# X8-Backplane.net
KiCad netlist of a schematic drawn in EAGLE
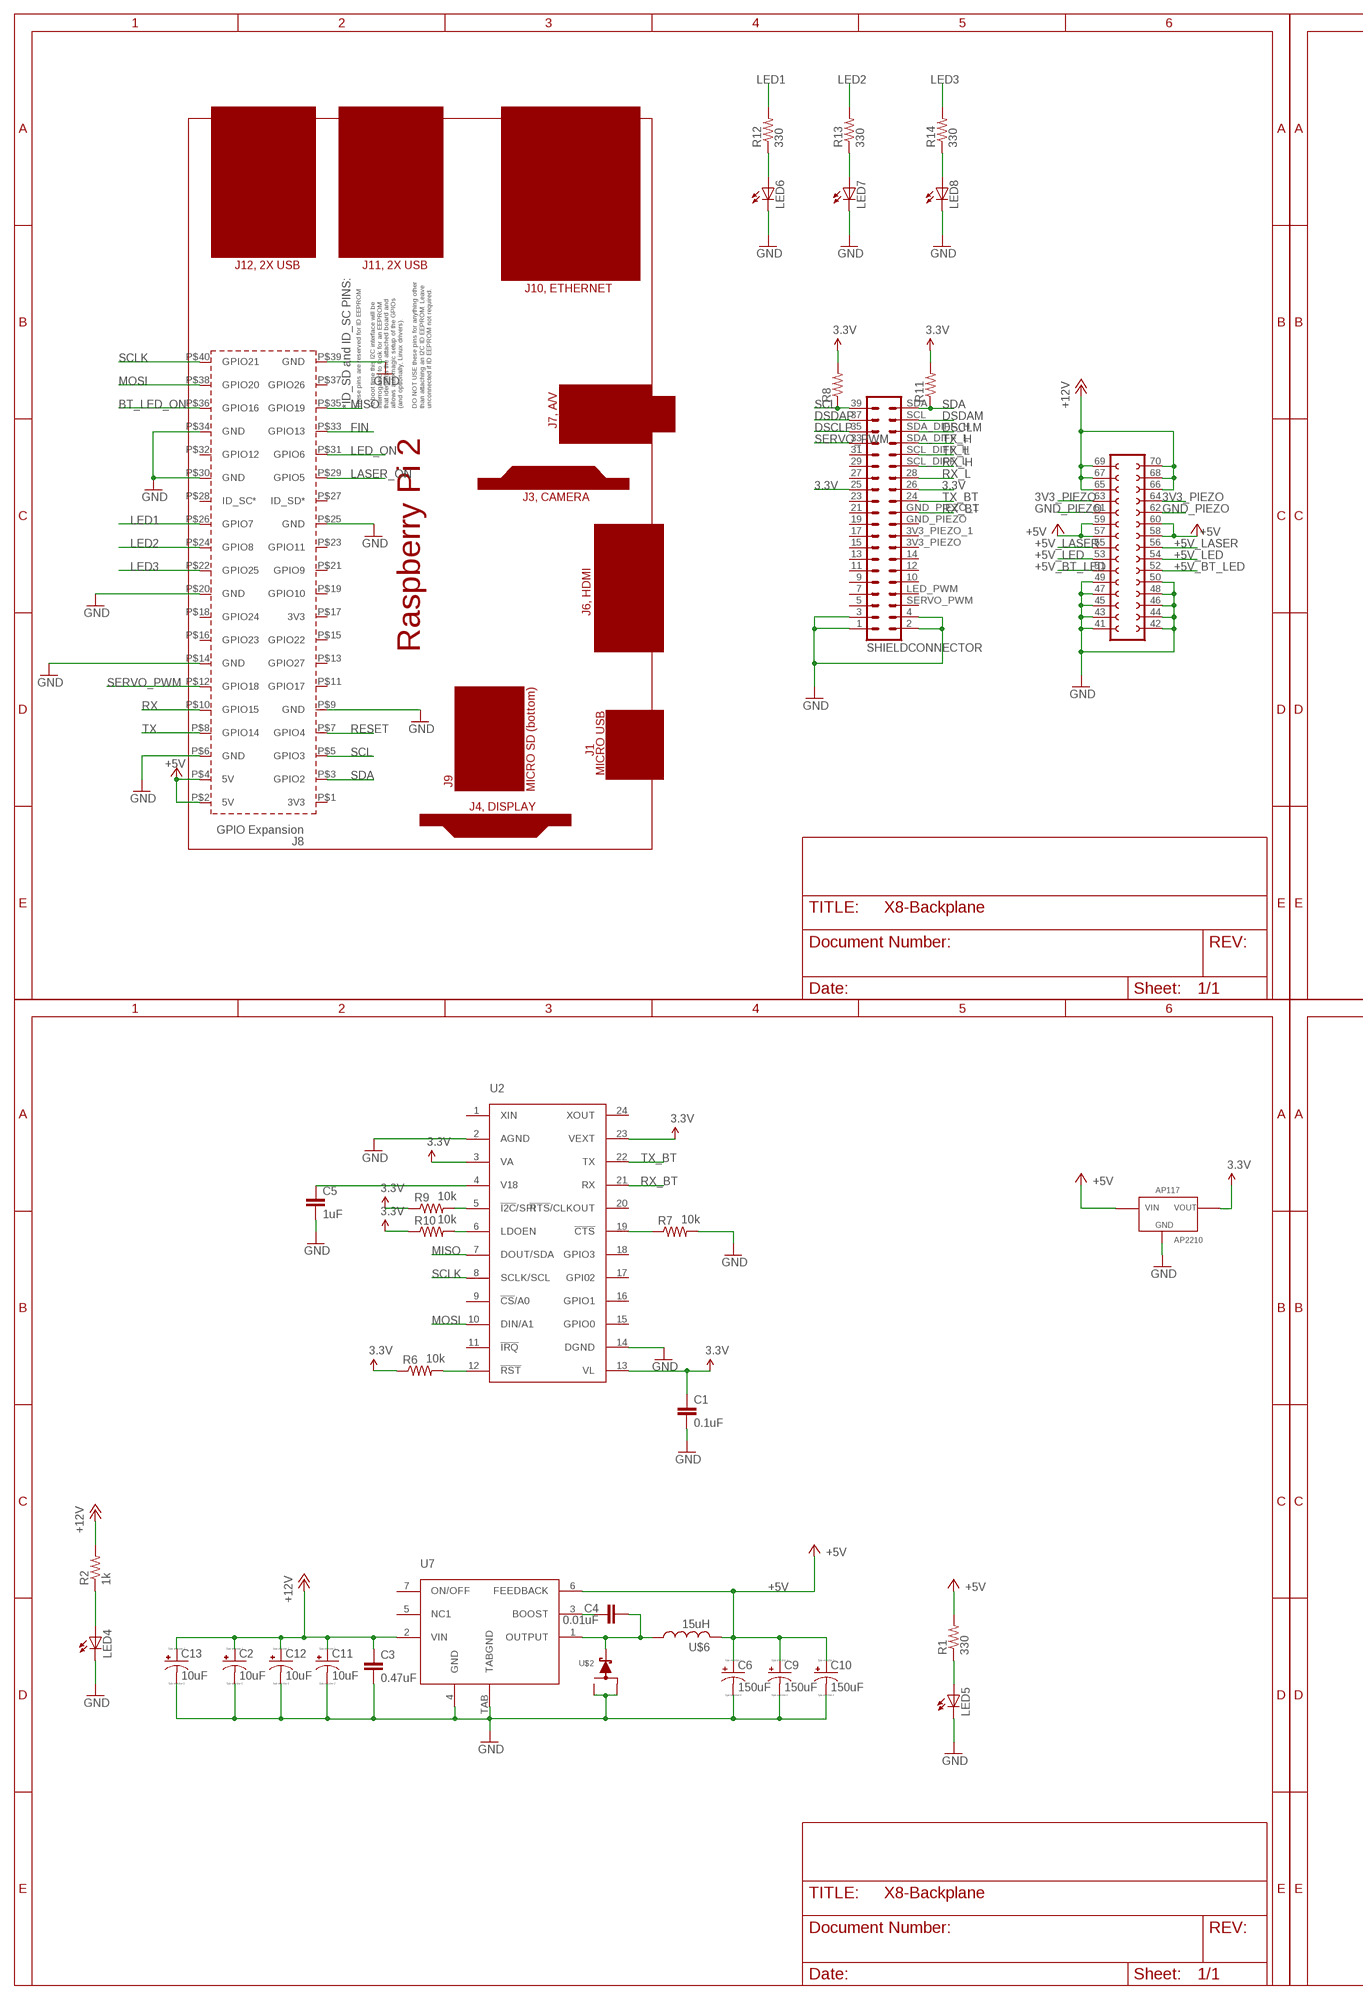
[diagram p0: schematic, sheet 1, part 1 of 2]
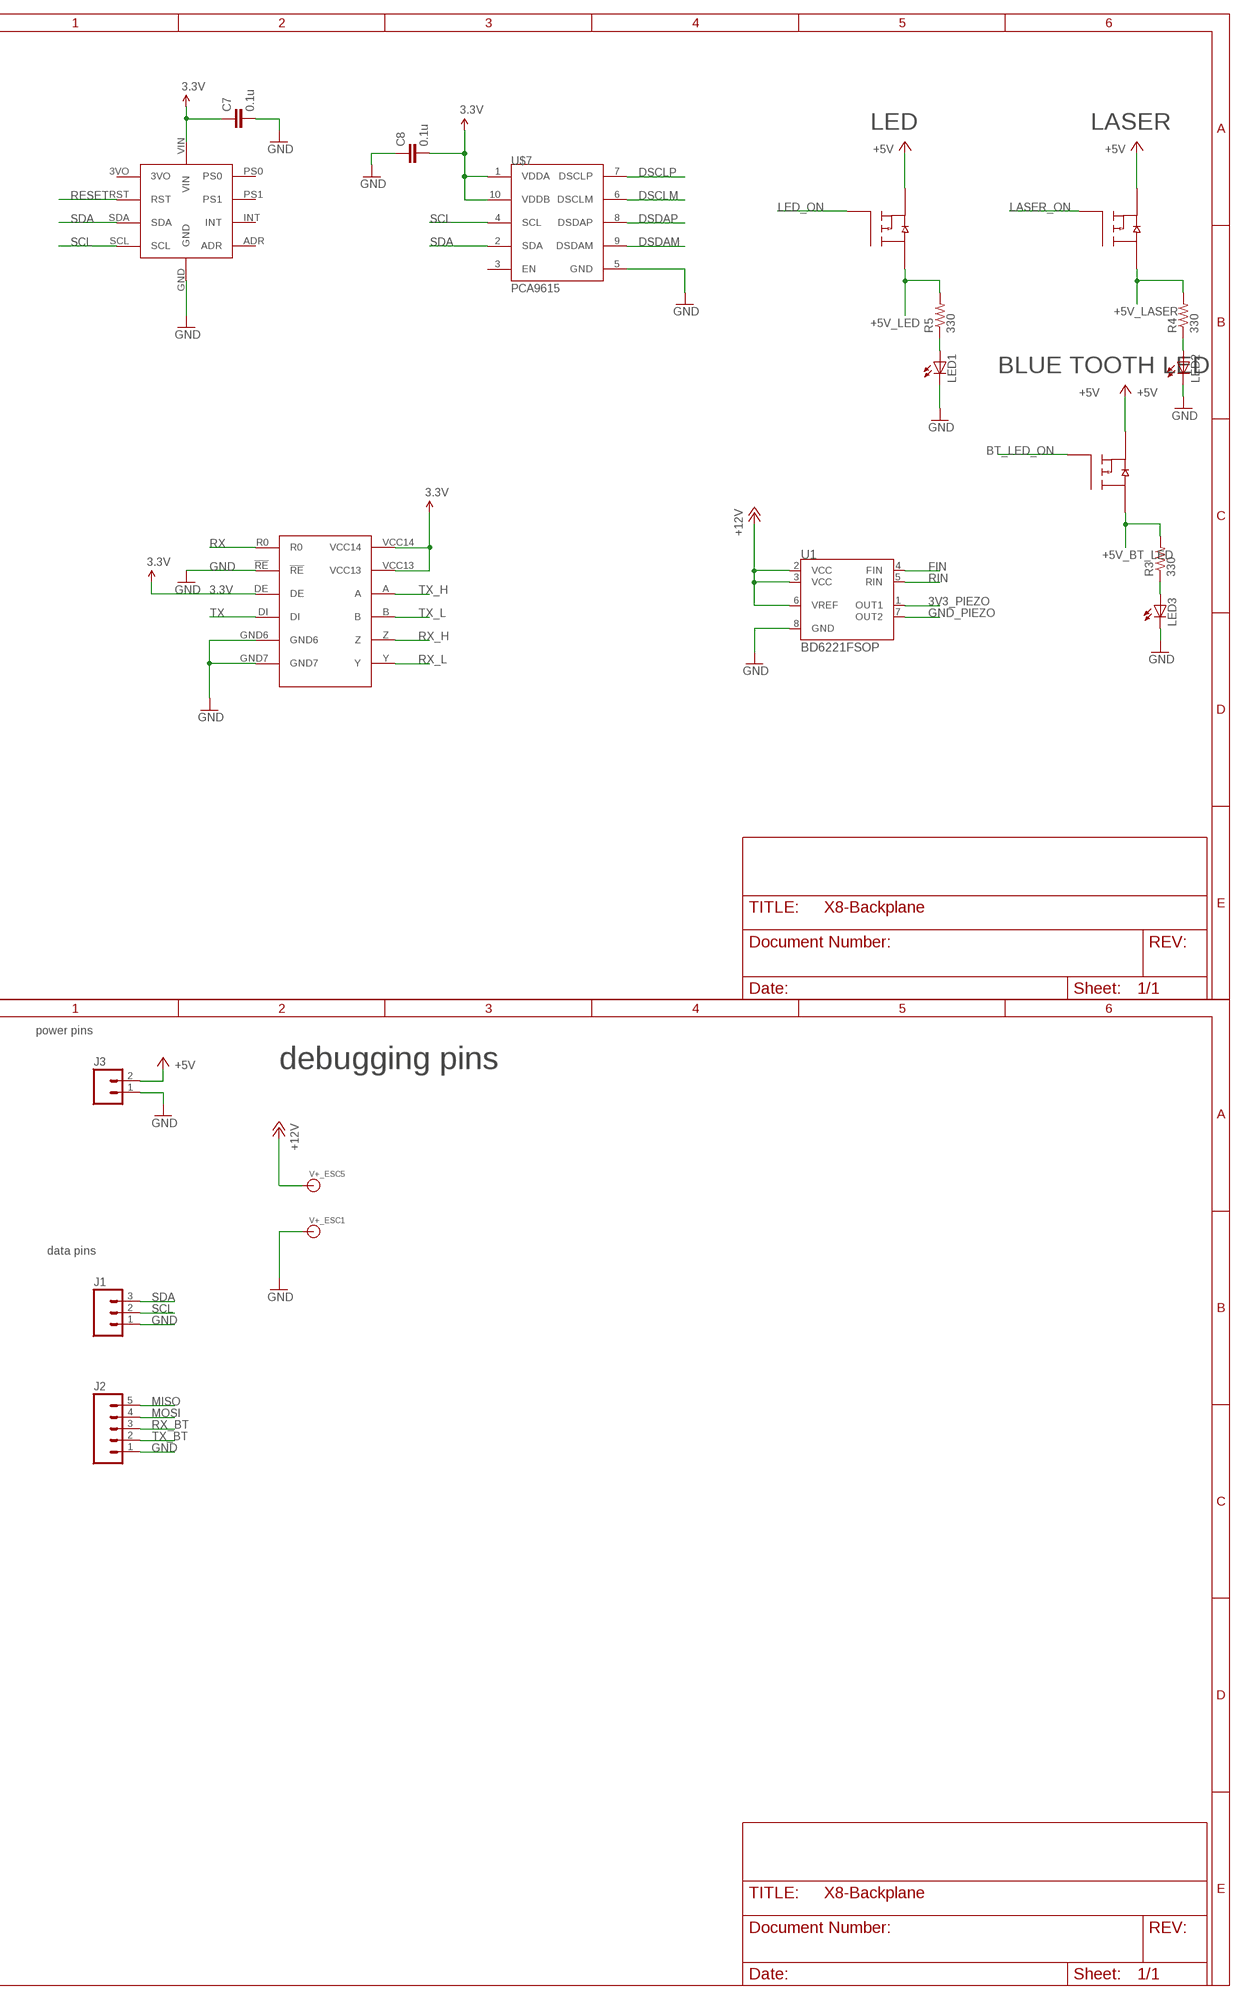
[diagram p1: schematic, sheet 1, part 2 of 2]

(export (version "E")
  (design (tool "Eeschema 10.0.6"))
  (components
    (comp (ref "C1")
      (value "0.1uF")
      (footprint "eagle-import:0603-CAP")
      (libsource (lib "eagle-import") (part "0.1UF-25V(+80/-20%)(0603)"))
    )
    (comp (ref "C2")
      (value "10uF")
      (footprint "eagle-import:CTAN(7.30_4.30MM)")
      (libsource (lib "eagle-import") (part "C-TANTALUM(10UF_150UF)"))
    )
    (comp (ref "C3")
      (value "0.47uF")
      (footprint "eagle-import:0603")
      (libsource (lib "eagle-import") (part "0.18UF-0603-10V-10%"))
    )
    (comp (ref "C4")
      (value "0.01uF")
      (footprint "eagle-import:0603-CAP")
      (libsource (lib "eagle-import") (part "CAP0603-CAP"))
    )
    (comp (ref "C5")
      (value "1uF")
      (footprint "eagle-import:0603-CAP")
      (libsource (lib "eagle-import") (part "0.1UF-25V(+80/-20%)(0603)"))
    )
    (comp (ref "C6")
      (value "150uF")
      (footprint "eagle-import:CTAN(7.30_4.30MM)")
      (libsource (lib "eagle-import") (part "C-TANTALUM(10UF_150UF)"))
    )
    (comp (ref "C7")
      (value "0.1u")
      (footprint "eagle-import:0603-CAP")
      (libsource (lib "eagle-import") (part "CAP0603-CAP"))
    )
    (comp (ref "C8")
      (value "0.1u")
      (footprint "eagle-import:0603-CAP")
      (libsource (lib "eagle-import") (part "CAP0603-CAP"))
    )
    (comp (ref "C9")
      (value "150uF")
      (footprint "eagle-import:CTAN(7.30_4.30MM)")
      (libsource (lib "eagle-import") (part "C-TANTALUM(10UF_150UF)"))
    )
    (comp (ref "C10")
      (value "150uF")
      (footprint "eagle-import:CTAN(7.30_4.30MM)")
      (libsource (lib "eagle-import") (part "C-TANTALUM(10UF_150UF)"))
    )
    (comp (ref "C11")
      (value "10uF")
      (footprint "eagle-import:CTAN(7.30_4.30MM)")
      (libsource (lib "eagle-import") (part "C-TANTALUM(10UF_150UF)"))
    )
    (comp (ref "C12")
      (value "10uF")
      (footprint "eagle-import:CTAN(7.30_4.30MM)")
      (libsource (lib "eagle-import") (part "C-TANTALUM(10UF_150UF)"))
    )
    (comp (ref "C13")
      (value "10uF")
      (footprint "eagle-import:CTAN(7.30_4.30MM)")
      (libsource (lib "eagle-import") (part "C-TANTALUM(10UF_150UF)"))
    )
    (comp (ref "J1")
      (value "M03PTH")
      (footprint "eagle-import:1X03")
      (libsource (lib "eagle-import") (part "M03PTH"))
    )
    (comp (ref "J2")
      (value "M05PTH")
      (footprint "eagle-import:1X05")
      (libsource (lib "eagle-import") (part "M05PTH"))
    )
    (comp (ref "J3")
      (value "M02PTH")
      (footprint "eagle-import:1X02")
      (libsource (lib "eagle-import") (part "M02PTH"))
    )
    (comp (ref "LED1")
      (value "LEDSML0603")
      (footprint "eagle-import:SML0603")
      (libsource (lib "eagle-import") (part "LEDSML0603"))
    )
    (comp (ref "LED2")
      (value "LEDSML0603")
      (footprint "eagle-import:SML0603")
      (libsource (lib "eagle-import") (part "LEDSML0603"))
    )
    (comp (ref "LED3")
      (value "LEDSML0603")
      (footprint "eagle-import:SML0603")
      (libsource (lib "eagle-import") (part "LEDSML0603"))
    )
    (comp (ref "LED4")
      (value "LEDSML0603")
      (footprint "eagle-import:SML0603")
      (libsource (lib "eagle-import") (part "LEDSML0603"))
    )
    (comp (ref "LED5")
      (value "LEDSML0603")
      (footprint "eagle-import:SML0603")
      (libsource (lib "eagle-import") (part "LEDSML0603"))
    )
    (comp (ref "LED6")
      (value "LEDSML0603")
      (footprint "eagle-import:SML0603")
      (libsource (lib "eagle-import") (part "LEDSML0603"))
    )
    (comp (ref "LED7")
      (value "LEDSML0603")
      (footprint "eagle-import:SML0603")
      (libsource (lib "eagle-import") (part "LEDSML0603"))
    )
    (comp (ref "LED8")
      (value "LEDSML0603")
      (footprint "eagle-import:SML0603")
      (libsource (lib "eagle-import") (part "LEDSML0603"))
    )
    (comp (ref "PCB1")
      (value "RPI2")
      (footprint "eagle-import:RPI2")
      (libsource (lib "eagle-import") (part "RPI2"))
    )
    (comp (ref "R1")
      (value "330")
      (footprint "eagle-import:R0603")
      (libsource (lib "eagle-import") (part "R-US_R0603"))
    )
    (comp (ref "R2")
      (value "1k")
      (footprint "eagle-import:R0603")
      (libsource (lib "eagle-import") (part "R-US_R0603"))
    )
    (comp (ref "R3")
      (value "330")
      (footprint "eagle-import:R0603")
      (libsource (lib "eagle-import") (part "R-US_R0603"))
    )
    (comp (ref "R4")
      (value "330")
      (footprint "eagle-import:R0603")
      (libsource (lib "eagle-import") (part "R-US_R0603"))
    )
    (comp (ref "R5")
      (value "330")
      (footprint "eagle-import:R0603")
      (libsource (lib "eagle-import") (part "R-US_R0603"))
    )
    (comp (ref "R6")
      (value "10k")
      (footprint "eagle-import:0603-RES")
      (libsource (lib "eagle-import") (part "RESISTOR0603-RES"))
    )
    (comp (ref "R7")
      (value "10k")
      (footprint "eagle-import:0603-RES")
      (libsource (lib "eagle-import") (part "RESISTOR0603-RES"))
    )
    (comp (ref "R8")
      (value "RESISTOR0603-RES")
      (footprint "eagle-import:0603-RES")
      (libsource (lib "eagle-import") (part "RESISTOR0603-RES"))
    )
    (comp (ref "R9")
      (value "10k")
      (footprint "eagle-import:0603-RES")
      (libsource (lib "eagle-import") (part "RESISTOR0603-RES"))
    )
    (comp (ref "R10")
      (value "10k")
      (footprint "eagle-import:0603-RES")
      (libsource (lib "eagle-import") (part "RESISTOR0603-RES"))
    )
    (comp (ref "R11")
      (value "RESISTOR0603-RES")
      (footprint "eagle-import:0603-RES")
      (libsource (lib "eagle-import") (part "RESISTOR0603-RES"))
    )
    (comp (ref "R12")
      (value "330")
      (footprint "eagle-import:R0603")
      (libsource (lib "eagle-import") (part "R-US_R0603"))
    )
    (comp (ref "R13")
      (value "330")
      (footprint "eagle-import:R0603")
      (libsource (lib "eagle-import") (part "R-US_R0603"))
    )
    (comp (ref "R14")
      (value "330")
      (footprint "eagle-import:R0603")
      (libsource (lib "eagle-import") (part "R-US_R0603"))
    )
    (comp (ref "U$1")
      (value "MAX3491")
      (footprint "eagle-import:MAX3491")
      (libsource (lib "eagle-import") (part "MAX3491"))
    )
    (comp (ref "U$2")
      (value "SWITCHMODE_SCHOTTKY")
      (footprint "eagle-import:DPAK-3")
      (libsource (lib "eagle-import") (part "SWITCHMODE_SCHOTTKY"))
    )
    (comp (ref "U$3")
      (value "BNO055_9DOF_BREAKOUT")
      (footprint "eagle-import:BNO055")
      (libsource (lib "eagle-import") (part "BNO055_9DOF_BREAKOUT"))
    )
    (comp (ref "U$4")
      (value "SHIELDCONNECTOR")
      (footprint "eagle-import:20X2PIN")
      (libsource (lib "eagle-import") (part "SHIELDCONNECTOR"))
    )
    (comp (ref "U$5")
      (value "AP2210")
      (footprint "eagle-import:SOT-23-3")
      (libsource (lib "eagle-import") (part "AP2210"))
    )
    (comp (ref "U$6")
      (value "15uH")
      (footprint "eagle-import:HCMA1305")
      (libsource (lib "eagle-import") (part "HCMA1305"))
    )
    (comp (ref "U$7")
      (value "PCA9615")
      (footprint "eagle-import:MSOP_10")
      (libsource (lib "eagle-import") (part "PCA9615"))
    )
    (comp (ref "U1")
      (value "BD6221FSOP")
      (footprint "eagle-import:SOP8")
      (libsource (lib "eagle-import") (part "BD6221FSOP"))
    )
    (comp (ref "U2")
      (value "MAX3107SSOP")
      (footprint "eagle-import:SSOP-24")
      (libsource (lib "eagle-import") (part "MAX3107SSOP"))
    )
    (comp (ref "U4")
      (value "FQB27P06")
      (footprint "eagle-import:TO263-3")
      (libsource (lib "eagle-import") (part "FQB27P06"))
    )
    (comp (ref "U5")
      (value "FQB27P06")
      (footprint "eagle-import:TO263-3")
      (libsource (lib "eagle-import") (part "FQB27P06"))
    )
    (comp (ref "U6")
      (value "FQB27P06")
      (footprint "eagle-import:TO263-3")
      (libsource (lib "eagle-import") (part "FQB27P06"))
    )
    (comp (ref "U7")
      (value "LM2678")
      (footprint "eagle-import:LM2678")
      (libsource (lib "eagle-import") (part "LM2678"))
    )
    (comp (ref "V+_ESC1")
      (value "BANANA_CONN")
      (footprint "eagle-import:BANANA_CONN")
      (libsource (lib "eagle-import") (part "BANANA_CONN"))
    )
    (comp (ref "V+_ESC5")
      (value "BANANA_CONN")
      (footprint "eagle-import:BANANA_CONN")
      (libsource (lib "eagle-import") (part "BANANA_CONN"))
    )
  )
  (nets
    (net (code "1") (name "+5V") (class "Default")
      (node (ref "C10") (pin "+") (pinfunction "+_+") (pintype "passive"))
      (node (ref "C6") (pin "+") (pinfunction "+_+") (pintype "passive"))
      (node (ref "C9") (pin "+") (pinfunction "+_+") (pintype "passive"))
      (node (ref "J3") (pin "2") (pinfunction "2_2") (pintype "passive"))
      (node (ref "PCB1") (pin "P$2") (pinfunction "5V_P$2") (pintype "bidirectional"))
      (node (ref "PCB1") (pin "P$4") (pinfunction "5V_P$4") (pintype "bidirectional"))
      (node (ref "R1") (pin "2") (pinfunction "2_2") (pintype "passive"))
      (node (ref "U$4") (pin "57") (pinfunction "17_57") (pintype "passive"))
      (node (ref "U$4") (pin "58") (pinfunction "18_58") (pintype "passive"))
      (node (ref "U$4") (pin "59") (pinfunction "19_59") (pintype "passive"))
      (node (ref "U$4") (pin "60") (pinfunction "20_60") (pintype "passive"))
      (node (ref "U$5") (pin "VIN") (pinfunction "VIN_VIN") (pintype "input"))
      (node (ref "U$6") (pin "P$2") (pinfunction "2_P$2") (pintype "passive"))
      (node (ref "U4") (pin "3") (pinfunction "S2_3") (pintype "bidirectional"))
      (node (ref "U5") (pin "3") (pinfunction "S2_3") (pintype "bidirectional"))
      (node (ref "U6") (pin "3") (pinfunction "S2_3") (pintype "bidirectional"))
      (node (ref "U7") (pin "6") (pinfunction "FEEDBACK_6") (pintype "bidirectional"))
    )
    (net (code "2") (name "+12V") (class "Default")
      (node (ref "C11") (pin "+") (pinfunction "+_+") (pintype "passive"))
      (node (ref "C12") (pin "+") (pinfunction "+_+") (pintype "passive"))
      (node (ref "C13") (pin "+") (pinfunction "+_+") (pintype "passive"))
      (node (ref "C2") (pin "+") (pinfunction "+_+") (pintype "passive"))
      (node (ref "C3") (pin "1") (pinfunction "1_1") (pintype "passive"))
      (node (ref "R2") (pin "2") (pinfunction "2_2") (pintype "passive"))
      (node (ref "U$4") (pin "65") (pinfunction "25_65") (pintype "passive"))
      (node (ref "U$4") (pin "66") (pinfunction "26_66") (pintype "passive"))
      (node (ref "U$4") (pin "67") (pinfunction "27_67") (pintype "passive"))
      (node (ref "U$4") (pin "68") (pinfunction "28_68") (pintype "passive"))
      (node (ref "U$4") (pin "69") (pinfunction "12V_69") (pintype "passive"))
      (node (ref "U$4") (pin "70") (pinfunction "30_70") (pintype "passive"))
      (node (ref "U1") (pin "2") (pinfunction "VCC_2") (pintype "power_in"))
      (node (ref "U1") (pin "3") (pinfunction "VCC_3") (pintype "power_in"))
      (node (ref "U1") (pin "6") (pinfunction "VREF_6") (pintype "bidirectional"))
      (node (ref "U7") (pin "2") (pinfunction "VIN_2") (pintype "bidirectional"))
      (node (ref "V+_ESC5") (pin "P$1") (pinfunction "1_P$1") (pintype "passive"))
    )
    (net (code "3") (name "/+5V_BT_LED") (class "Default")
      (node (ref "R3") (pin "2") (pinfunction "2_2") (pintype "passive"))
      (node (ref "U$4") (pin "51") (pinfunction "11_51") (pintype "passive"))
      (node (ref "U$4") (pin "52") (pinfunction "12_52") (pintype "passive"))
      (node (ref "U6") (pin "TAB") (pinfunction "D2_TAB") (pintype "bidirectional"))
    )
    (net (code "4") (name "/+5V_LASER") (class "Default")
      (node (ref "R4") (pin "2") (pinfunction "2_2") (pintype "passive"))
      (node (ref "U$4") (pin "55") (pinfunction "15_55") (pintype "passive"))
      (node (ref "U$4") (pin "56") (pinfunction "16_56") (pintype "passive"))
      (node (ref "U5") (pin "TAB") (pinfunction "D2_TAB") (pintype "bidirectional"))
    )
    (net (code "5") (name "/+5V_LED") (class "Default")
      (node (ref "R5") (pin "2") (pinfunction "2_2") (pintype "passive"))
      (node (ref "U$4") (pin "53") (pinfunction "13_53") (pintype "passive"))
      (node (ref "U$4") (pin "54") (pinfunction "14_54") (pintype "passive"))
      (node (ref "U4") (pin "TAB") (pinfunction "D2_TAB") (pintype "bidirectional"))
    )
    (net (code "6") (name "/3V3_PIEZO") (class "Default")
      (node (ref "U$4") (pin "63") (pinfunction "23_63") (pintype "passive"))
      (node (ref "U$4") (pin "64") (pinfunction "24_64") (pintype "passive"))
      (node (ref "U1") (pin "1") (pinfunction "OUT1_1") (pintype "output"))
    )
    (net (code "7") (name "/BT_LED_ON") (class "Default")
      (node (ref "PCB1") (pin "P$36") (pinfunction "GPIO16_P$36") (pintype "bidirectional"))
      (node (ref "U6") (pin "1") (pinfunction "G2_1") (pintype "bidirectional"))
    )
    (net (code "8") (name "/DSCLM") (class "Default")
      (node (ref "U$4") (pin "SDA_DIFF_H") (pinfunction "SDA_DIFF_H_SDA_DIFF_H") (pintype "passive"))
      (node (ref "U$7") (pin "6") (pinfunction "DSCLM_6") (pintype "bidirectional"))
    )
    (net (code "9") (name "/DSCLP") (class "Default")
      (node (ref "U$4") (pin "35") (pinfunction "35_35") (pintype "passive"))
      (node (ref "U$7") (pin "7") (pinfunction "DSCLP_7") (pintype "bidirectional"))
    )
    (net (code "10") (name "/DSDAM") (class "Default")
      (node (ref "U$4") (pin "SCL") (pinfunction "SCL_SCL") (pintype "passive"))
      (node (ref "U$7") (pin "9") (pinfunction "DSDAM_9") (pintype "bidirectional"))
    )
    (net (code "11") (name "/DSDAP") (class "Default")
      (node (ref "U$4") (pin "37") (pinfunction "37_37") (pintype "passive"))
      (node (ref "U$7") (pin "8") (pinfunction "DSDAP_8") (pintype "bidirectional"))
    )
    (net (code "12") (name "/FIN") (class "Default")
      (node (ref "PCB1") (pin "P$33") (pinfunction "GPIO13_P$33") (pintype "bidirectional"))
      (node (ref "U1") (pin "4") (pinfunction "FIN_4") (pintype "input"))
    )
    (net (code "13") (name "/GND_PIEZO") (class "Default")
      (node (ref "U$4") (pin "61") (pinfunction "21_61") (pintype "passive"))
      (node (ref "U$4") (pin "62") (pinfunction "22_62") (pintype "passive"))
      (node (ref "U1") (pin "7") (pinfunction "OUT2_7") (pintype "output"))
    )
    (net (code "14") (name "/LASER_ON") (class "Default")
      (node (ref "PCB1") (pin "P$29") (pinfunction "GPIO5_P$29") (pintype "bidirectional"))
      (node (ref "U5") (pin "1") (pinfunction "G2_1") (pintype "bidirectional"))
    )
    (net (code "15") (name "/LED1") (class "Default")
      (node (ref "PCB1") (pin "P$26") (pinfunction "GPIO7_P$26") (pintype "bidirectional"))
      (node (ref "R12") (pin "2") (pinfunction "2_2") (pintype "passive"))
    )
    (net (code "16") (name "/LED2") (class "Default")
      (node (ref "PCB1") (pin "P$24") (pinfunction "GPIO8_P$24") (pintype "bidirectional"))
      (node (ref "R13") (pin "2") (pinfunction "2_2") (pintype "passive"))
    )
    (net (code "17") (name "/LED3") (class "Default")
      (node (ref "PCB1") (pin "P$22") (pinfunction "GPIO25_P$22") (pintype "bidirectional"))
      (node (ref "R14") (pin "2") (pinfunction "2_2") (pintype "passive"))
    )
    (net (code "18") (name "/LED_ON") (class "Default")
      (node (ref "PCB1") (pin "P$31") (pinfunction "GPIO6_P$31") (pintype "bidirectional"))
      (node (ref "U4") (pin "1") (pinfunction "G2_1") (pintype "bidirectional"))
    )
    (net (code "19") (name "/MISO") (class "Default")
      (node (ref "J2") (pin "5") (pinfunction "5_5") (pintype "passive"))
      (node (ref "PCB1") (pin "P$35") (pinfunction "GPIO19_P$35") (pintype "bidirectional"))
      (node (ref "U2") (pin "7") (pinfunction "DOUT/SDA_7") (pintype "bidirectional"))
    )
    (net (code "20") (name "/MOSI") (class "Default")
      (node (ref "J2") (pin "4") (pinfunction "4_4") (pintype "passive"))
      (node (ref "PCB1") (pin "P$38") (pinfunction "GPIO20_P$38") (pintype "bidirectional"))
      (node (ref "U2") (pin "10") (pinfunction "DIN/A1_10") (pintype "bidirectional"))
    )
    (net (code "21") (name "/RESET") (class "Default")
      (node (ref "PCB1") (pin "P$7") (pinfunction "GPIO4_P$7") (pintype "bidirectional"))
      (node (ref "U$3") (pin "RST") (pinfunction "RST_RST") (pintype "bidirectional"))
    )
    (net (code "22") (name "/RIN") (class "Default")
      (node (ref "U1") (pin "5") (pinfunction "RIN_5") (pintype "input"))
    )
    (net (code "23") (name "/RX") (class "Default")
      (node (ref "PCB1") (pin "P$10") (pinfunction "GPIO15_P$10") (pintype "bidirectional"))
      (node (ref "U$1") (pin "R0") (pinfunction "R0_R0") (pintype "bidirectional"))
    )
    (net (code "24") (name "/RX_BT") (class "Default")
      (node (ref "J2") (pin "3") (pinfunction "3_3") (pintype "passive"))
      (node (ref "U$4") (pin "GND_PIEZO_1") (pinfunction "GND_PIEZO_1_GND_PIEZO_1") (pintype "passive"))
      (node (ref "U2") (pin "21") (pinfunction "RX_21") (pintype "bidirectional"))
    )
    (net (code "25") (name "/RX_H") (class "Default")
      (node (ref "U$1") (pin "Z") (pinfunction "Z_Z") (pintype "bidirectional"))
      (node (ref "U$4") (pin "SCL_DIFF_L") (pinfunction "SCL_DIFF_L_SCL_DIFF_L") (pintype "passive"))
    )
    (net (code "26") (name "/RX_L") (class "Default")
      (node (ref "U$1") (pin "Y") (pinfunction "Y_Y") (pintype "bidirectional"))
      (node (ref "U$4") (pin "28") (pinfunction "28_28") (pintype "passive"))
    )
    (net (code "27") (name "/SCL") (class "Default")
      (node (ref "J1") (pin "2") (pinfunction "2_2") (pintype "passive"))
      (node (ref "PCB1") (pin "P$5") (pinfunction "GPIO3_P$5") (pintype "bidirectional"))
      (node (ref "R8") (pin "1") (pinfunction "1_1") (pintype "passive"))
      (node (ref "U$3") (pin "SCL") (pinfunction "SCL_SCL") (pintype "bidirectional"))
      (node (ref "U$4") (pin "39") (pinfunction "39_39") (pintype "passive"))
      (node (ref "U$7") (pin "4") (pinfunction "SCL_4") (pintype "bidirectional"))
    )
    (net (code "28") (name "/SCLK") (class "Default")
      (node (ref "PCB1") (pin "P$40") (pinfunction "GPIO21_P$40") (pintype "bidirectional"))
      (node (ref "U2") (pin "8") (pinfunction "SCLK/SCL_8") (pintype "bidirectional"))
    )
    (net (code "29") (name "/SDA") (class "Default")
      (node (ref "J1") (pin "3") (pinfunction "3_3") (pintype "passive"))
      (node (ref "PCB1") (pin "P$3") (pinfunction "GPIO2_P$3") (pintype "bidirectional"))
      (node (ref "R11") (pin "1") (pinfunction "1_1") (pintype "passive"))
      (node (ref "U$3") (pin "SDA") (pinfunction "SDA_SDA") (pintype "bidirectional"))
      (node (ref "U$4") (pin "SDA") (pinfunction "SDA_SDA") (pintype "passive"))
      (node (ref "U$7") (pin "2") (pinfunction "SDA_2") (pintype "bidirectional"))
    )
    (net (code "30") (name "/SERVO_PWM") (class "Default")
      (node (ref "PCB1") (pin "P$12") (pinfunction "GPIO18_P$12") (pintype "bidirectional"))
      (node (ref "U$4") (pin "33") (pinfunction "33_33") (pintype "passive"))
    )
    (net (code "31") (name "/TX") (class "Default")
      (node (ref "PCB1") (pin "P$8") (pinfunction "GPIO14_P$8") (pintype "bidirectional"))
      (node (ref "U$1") (pin "DI") (pinfunction "DI_DI") (pintype "bidirectional"))
    )
    (net (code "32") (name "/TX_BT") (class "Default")
      (node (ref "J2") (pin "2") (pinfunction "2_2") (pintype "passive"))
      (node (ref "U$4") (pin "24") (pinfunction "24_24") (pintype "passive"))
      (node (ref "U2") (pin "22") (pinfunction "TX_22") (pintype "bidirectional"))
    )
    (net (code "33") (name "/TX_H") (class "Default")
      (node (ref "U$1") (pin "A") (pinfunction "A_A") (pintype "bidirectional"))
      (node (ref "U$4") (pin "SDA_DIFF_L") (pinfunction "SDA_DIFF_L_SDA_DIFF_L") (pintype "passive"))
    )
    (net (code "34") (name "/TX_L") (class "Default")
      (node (ref "U$1") (pin "B") (pinfunction "B_B") (pintype "bidirectional"))
      (node (ref "U$4") (pin "SCL_DIFF_H") (pinfunction "SCL_DIFF_H_SCL_DIFF_H") (pintype "passive"))
    )
    (net (code "35") (name "3.3V") (class "Default")
      (node (ref "C1") (pin "1") (pinfunction "1_1") (pintype "passive"))
      (node (ref "C7") (pin "1") (pinfunction "1_1") (pintype "passive"))
      (node (ref "C8") (pin "2") (pinfunction "2_2") (pintype "passive"))
      (node (ref "R10") (pin "1") (pinfunction "1_1") (pintype "passive"))
      (node (ref "R11") (pin "2") (pinfunction "2_2") (pintype "passive"))
      (node (ref "R6") (pin "1") (pinfunction "1_1") (pintype "passive"))
      (node (ref "R8") (pin "2") (pinfunction "2_2") (pintype "passive"))
      (node (ref "R9") (pin "1") (pinfunction "1_1") (pintype "passive"))
      (node (ref "U$1") (pin "DE") (pinfunction "DE_DE") (pintype "bidirectional"))
      (node (ref "U$1") (pin "VCC13") (pinfunction "VCC13_VCC13") (pintype "bidirectional"))
      (node (ref "U$1") (pin "VCC14") (pinfunction "VCC14_VCC14") (pintype "bidirectional"))
      (node (ref "U$3") (pin "VIN") (pinfunction "VIN_VIN") (pintype "bidirectional"))
      (node (ref "U$4") (pin "25") (pinfunction "25_25") (pintype "passive"))
      (node (ref "U$4") (pin "26") (pinfunction "26_26") (pintype "passive"))
      (node (ref "U$5") (pin "VOUT") (pinfunction "VOUT_VOUT") (pintype "output"))
      (node (ref "U$7") (pin "1") (pinfunction "VDDA_1") (pintype "bidirectional"))
      (node (ref "U$7") (pin "10") (pinfunction "VDDB_10") (pintype "bidirectional"))
      (node (ref "U2") (pin "13") (pinfunction "VL_13") (pintype "bidirectional"))
      (node (ref "U2") (pin "23") (pinfunction "VEXT_23") (pintype "bidirectional"))
      (node (ref "U2") (pin "3") (pinfunction "VA_3") (pintype "bidirectional"))
    )
    (net (code "36") (name "GND") (class "Default")
      (node (ref "C1") (pin "2") (pinfunction "2_2") (pintype "passive"))
      (node (ref "C10") (pin "-") (pinfunction "-_-") (pintype "passive"))
      (node (ref "C11") (pin "-") (pinfunction "-_-") (pintype "passive"))
      (node (ref "C12") (pin "-") (pinfunction "-_-") (pintype "passive"))
      (node (ref "C13") (pin "-") (pinfunction "-_-") (pintype "passive"))
      (node (ref "C2") (pin "-") (pinfunction "-_-") (pintype "passive"))
      (node (ref "C3") (pin "2") (pinfunction "2_2") (pintype "passive"))
      (node (ref "C5") (pin "2") (pinfunction "2_2") (pintype "passive"))
      (node (ref "C6") (pin "-") (pinfunction "-_-") (pintype "passive"))
      (node (ref "C7") (pin "2") (pinfunction "2_2") (pintype "passive"))
      (node (ref "C8") (pin "1") (pinfunction "1_1") (pintype "passive"))
      (node (ref "C9") (pin "-") (pinfunction "-_-") (pintype "passive"))
      (node (ref "J1") (pin "1") (pinfunction "1_1") (pintype "passive"))
      (node (ref "J2") (pin "1") (pinfunction "1_1") (pintype "passive"))
      (node (ref "J3") (pin "1") (pinfunction "1_1") (pintype "passive"))
      (node (ref "LED1") (pin "C") (pinfunction "C_C") (pintype "passive"))
      (node (ref "LED2") (pin "C") (pinfunction "C_C") (pintype "passive"))
      (node (ref "LED3") (pin "C") (pinfunction "C_C") (pintype "passive"))
      (node (ref "LED4") (pin "C") (pinfunction "C_C") (pintype "passive"))
      (node (ref "LED5") (pin "C") (pinfunction "C_C") (pintype "passive"))
      (node (ref "LED6") (pin "C") (pinfunction "C_C") (pintype "passive"))
      (node (ref "LED7") (pin "C") (pinfunction "C_C") (pintype "passive"))
      (node (ref "LED8") (pin "C") (pinfunction "C_C") (pintype "passive"))
      (node (ref "PCB1") (pin "P$14") (pinfunction "GND_P$14") (pintype "bidirectional"))
      (node (ref "PCB1") (pin "P$20") (pinfunction "GND_P$20") (pintype "bidirectional"))
      (node (ref "PCB1") (pin "P$25") (pinfunction "GND_P$25") (pintype "bidirectional"))
      (node (ref "PCB1") (pin "P$30") (pinfunction "GND_P$30") (pintype "bidirectional"))
      (node (ref "PCB1") (pin "P$34") (pinfunction "GND_P$34") (pintype "bidirectional"))
      (node (ref "PCB1") (pin "P$39") (pinfunction "GND_P$39") (pintype "bidirectional"))
      (node (ref "PCB1") (pin "P$6") (pinfunction "GND_P$6") (pintype "bidirectional"))
      (node (ref "PCB1") (pin "P$9") (pinfunction "GND_P$9") (pintype "bidirectional"))
      (node (ref "R7") (pin "2") (pinfunction "2_2") (pintype "passive"))
      (node (ref "U$1") (pin "!RE") (pinfunction "~{RE}_!RE") (pintype "bidirectional"))
      (node (ref "U$1") (pin "GND6") (pinfunction "GND6_GND6") (pintype "bidirectional"))
      (node (ref "U$1") (pin "GND7") (pinfunction "GND7_GND7") (pintype "bidirectional"))
      (node (ref "U$2") (pin "P$1") (pinfunction "P$1_P$1") (pintype "bidirectional"))
      (node (ref "U$2") (pin "P$3") (pinfunction "P$3_P$3") (pintype "bidirectional"))
      (node (ref "U$3") (pin "GND") (pinfunction "GND_GND") (pintype "bidirectional"))
      (node (ref "U$4") (pin "1") (pinfunction "1_1") (pintype "passive"))
      (node (ref "U$4") (pin "2") (pinfunction "2_2") (pintype "passive"))
      (node (ref "U$4") (pin "3") (pinfunction "3_3") (pintype "passive"))
      (node (ref "U$4") (pin "4") (pinfunction "4_4") (pintype "passive"))
      (node (ref "U$4") (pin "41") (pinfunction "1_41") (pintype "passive"))
      (node (ref "U$4") (pin "42") (pinfunction "2_42") (pintype "passive"))
      (node (ref "U$4") (pin "43") (pinfunction "3_43") (pintype "passive"))
      (node (ref "U$4") (pin "44") (pinfunction "4_44") (pintype "passive"))
      (node (ref "U$4") (pin "45") (pinfunction "5_45") (pintype "passive"))
      (node (ref "U$4") (pin "46") (pinfunction "6_46") (pintype "passive"))
      (node (ref "U$4") (pin "47") (pinfunction "7_47") (pintype "passive"))
      (node (ref "U$4") (pin "48") (pinfunction "8_48") (pintype "passive"))
      (node (ref "U$4") (pin "49") (pinfunction "9_49") (pintype "passive"))
      (node (ref "U$4") (pin "50") (pinfunction "10_50") (pintype "passive"))
      (node (ref "U$5") (pin "GND") (pinfunction "GND_GND") (pintype "bidirectional"))
      (node (ref "U$7") (pin "5") (pinfunction "GND_5") (pintype "bidirectional"))
      (node (ref "U1") (pin "8") (pinfunction "GND_8") (pintype "power_in"))
      (node (ref "U2") (pin "14") (pinfunction "DGND_14") (pintype "bidirectional"))
      (node (ref "U2") (pin "2") (pinfunction "AGND_2") (pintype "bidirectional"))
      (node (ref "U7") (pin "4") (pinfunction "GND_4") (pintype "bidirectional"))
      (node (ref "U7") (pin "TAB") (pinfunction "TABGND_TAB") (pintype "bidirectional"))
      (node (ref "V+_ESC1") (pin "P$1") (pinfunction "1_P$1") (pintype "passive"))
    )
    (net (code "37") (name "Net-(LED1-PadA)") (class "Default")
      (node (ref "LED1") (pin "A") (pinfunction "A_A") (pintype "passive"))
      (node (ref "R5") (pin "1") (pinfunction "1_1") (pintype "passive"))
    )
    (net (code "38") (name "Net-(LED2-PadA)") (class "Default")
      (node (ref "LED2") (pin "A") (pinfunction "A_A") (pintype "passive"))
      (node (ref "R4") (pin "1") (pinfunction "1_1") (pintype "passive"))
    )
    (net (code "39") (name "Net-(LED3-PadA)") (class "Default")
      (node (ref "LED3") (pin "A") (pinfunction "A_A") (pintype "passive"))
      (node (ref "R3") (pin "1") (pinfunction "1_1") (pintype "passive"))
    )
    (net (code "40") (name "Net-(LED4-PadA)") (class "Default")
      (node (ref "LED4") (pin "A") (pinfunction "A_A") (pintype "passive"))
      (node (ref "R2") (pin "1") (pinfunction "1_1") (pintype "passive"))
    )
    (net (code "41") (name "Net-(LED5-PadA)") (class "Default")
      (node (ref "LED5") (pin "A") (pinfunction "A_A") (pintype "passive"))
      (node (ref "R1") (pin "1") (pinfunction "1_1") (pintype "passive"))
    )
    (net (code "42") (name "Net-(LED6-PadA)") (class "Default")
      (node (ref "LED6") (pin "A") (pinfunction "A_A") (pintype "passive"))
      (node (ref "R12") (pin "1") (pinfunction "1_1") (pintype "passive"))
    )
    (net (code "43") (name "Net-(LED7-PadA)") (class "Default")
      (node (ref "LED7") (pin "A") (pinfunction "A_A") (pintype "passive"))
      (node (ref "R13") (pin "1") (pinfunction "1_1") (pintype "passive"))
    )
    (net (code "44") (name "Net-(LED8-PadA)") (class "Default")
      (node (ref "LED8") (pin "A") (pinfunction "A_A") (pintype "passive"))
      (node (ref "R14") (pin "1") (pinfunction "1_1") (pintype "passive"))
    )
    (net (code "45") (name "Net-(U$6-1)") (class "Default")
      (node (ref "C4") (pin "2") (pinfunction "2_2") (pintype "passive"))
      (node (ref "U$2") (pin "P$4") (pinfunction "P$4_P$4") (pintype "bidirectional"))
      (node (ref "U$6") (pin "P$1") (pinfunction "1_P$1") (pintype "passive"))
      (node (ref "U7") (pin "1") (pinfunction "OUTPUT_1") (pintype "bidirectional"))
    )
    (net (code "46") (name "Net-(U2-LDOEN)") (class "Default")
      (node (ref "R10") (pin "2") (pinfunction "2_2") (pintype "passive"))
      (node (ref "U2") (pin "6") (pinfunction "LDOEN_6") (pintype "bidirectional"))
    )
    (net (code "47") (name "Net-(U2-V18)") (class "Default")
      (node (ref "C5") (pin "1") (pinfunction "1_1") (pintype "passive"))
      (node (ref "U2") (pin "4") (pinfunction "V18_4") (pintype "bidirectional"))
    )
    (net (code "48") (name "Net-(U2-~{CTS})") (class "Default")
      (node (ref "R7") (pin "1") (pinfunction "1_1") (pintype "passive"))
      (node (ref "U2") (pin "19") (pinfunction "~{CTS}_19") (pintype "bidirectional"))
    )
    (net (code "49") (name "Net-(U2-~{I2C}{slash}SPI)") (class "Default")
      (node (ref "R9") (pin "2") (pinfunction "2_2") (pintype "passive"))
      (node (ref "U2") (pin "5") (pinfunction "~{I2C}/SPI_5") (pintype "bidirectional"))
    )
    (net (code "50") (name "Net-(U2-~{RST})") (class "Default")
      (node (ref "R6") (pin "2") (pinfunction "2_2") (pintype "passive"))
      (node (ref "U2") (pin "12") (pinfunction "~{RST}_12") (pintype "bidirectional"))
    )
    (net (code "51") (name "Net-(U7-BOOST)") (class "Default")
      (node (ref "C4") (pin "1") (pinfunction "1_1") (pintype "passive"))
      (node (ref "U7") (pin "3") (pinfunction "BOOST_3") (pintype "bidirectional"))
    )
    (net (code "52") (name "unconnected-(PCB1-3V3-PadP$1)") (class "Default")
      (node (ref "PCB1") (pin "P$1") (pinfunction "3V3_P$1") (pintype "bidirectional"))
    )
    (net (code "53") (name "unconnected-(PCB1-3V3-PadP$17)") (class "Default")
      (node (ref "PCB1") (pin "P$17") (pinfunction "3V3_P$17") (pintype "bidirectional"))
    )
    (net (code "54") (name "unconnected-(PCB1-GPIO9-PadP$21)") (class "Default")
      (node (ref "PCB1") (pin "P$21") (pinfunction "GPIO9_P$21") (pintype "bidirectional"))
    )
    (net (code "55") (name "unconnected-(PCB1-GPIO10-PadP$19)") (class "Default")
      (node (ref "PCB1") (pin "P$19") (pinfunction "GPIO10_P$19") (pintype "bidirectional"))
    )
    (net (code "56") (name "unconnected-(PCB1-GPIO11-PadP$23)") (class "Default")
      (node (ref "PCB1") (pin "P$23") (pinfunction "GPIO11_P$23") (pintype "bidirectional"))
    )
    (net (code "57") (name "unconnected-(PCB1-GPIO12-PadP$32)") (class "Default")
      (node (ref "PCB1") (pin "P$32") (pinfunction "GPIO12_P$32") (pintype "bidirectional"))
    )
    (net (code "58") (name "unconnected-(PCB1-GPIO17-PadP$11)") (class "Default")
      (node (ref "PCB1") (pin "P$11") (pinfunction "GPIO17_P$11") (pintype "bidirectional"))
    )
    (net (code "59") (name "unconnected-(PCB1-GPIO22-PadP$15)") (class "Default")
      (node (ref "PCB1") (pin "P$15") (pinfunction "GPIO22_P$15") (pintype "bidirectional"))
    )
    (net (code "60") (name "unconnected-(PCB1-GPIO23-PadP$16)") (class "Default")
      (node (ref "PCB1") (pin "P$16") (pinfunction "GPIO23_P$16") (pintype "bidirectional"))
    )
    (net (code "61") (name "unconnected-(PCB1-GPIO24-PadP$18)") (class "Default")
      (node (ref "PCB1") (pin "P$18") (pinfunction "GPIO24_P$18") (pintype "bidirectional"))
    )
    (net (code "62") (name "unconnected-(PCB1-GPIO26-PadP$37)") (class "Default")
      (node (ref "PCB1") (pin "P$37") (pinfunction "GPIO26_P$37") (pintype "bidirectional"))
    )
    (net (code "63") (name "unconnected-(PCB1-GPIO27-PadP$13)") (class "Default")
      (node (ref "PCB1") (pin "P$13") (pinfunction "GPIO27_P$13") (pintype "bidirectional"))
    )
    (net (code "64") (name "unconnected-(PCB1-ID_SC*-PadP$28)") (class "Default")
      (node (ref "PCB1") (pin "P$28") (pinfunction "ID_SC*_P$28") (pintype "bidirectional"))
    )
    (net (code "65") (name "unconnected-(PCB1-ID_SD*-PadP$27)") (class "Default")
      (node (ref "PCB1") (pin "P$27") (pinfunction "ID_SD*_P$27") (pintype "bidirectional"))
    )
    (net (code "66") (name "unconnected-(U$3-Pad3VO)") (class "Default")
      (node (ref "U$3") (pin "3VO") (pinfunction "3VO_3VO") (pintype "bidirectional"))
    )
    (net (code "67") (name "unconnected-(U$3-PadADR)") (class "Default")
      (node (ref "U$3") (pin "ADR") (pinfunction "ADR_ADR") (pintype "bidirectional"))
    )
    (net (code "68") (name "unconnected-(U$3-PadINT)") (class "Default")
      (node (ref "U$3") (pin "INT") (pinfunction "INT_INT") (pintype "bidirectional"))
    )
    (net (code "69") (name "unconnected-(U$3-PadPS0)") (class "Default")
      (node (ref "U$3") (pin "PS0") (pinfunction "PS0_PS0") (pintype "bidirectional"))
    )
    (net (code "70") (name "unconnected-(U$3-PadPS1)") (class "Default")
      (node (ref "U$3") (pin "PS1") (pinfunction "PS1_PS1") (pintype "bidirectional"))
    )
    (net (code "71") (name "unconnected-(U$4-Pad3V3_PIEZO)") (class "Default")
      (node (ref "U$4") (pin "3V3_PIEZO") (pinfunction "3V3_PIEZO_3V3_PIEZO") (pintype "passive"))
    )
    (net (code "72") (name "unconnected-(U$4-Pad3V3_PIEZO_1)") (class "Default")
      (node (ref "U$4") (pin "3V3_PIEZO_1") (pinfunction "3V3_PIEZO_1_3V3_PIEZO_1") (pintype "passive"))
    )
    (net (code "73") (name "unconnected-(U$4-Pad5)") (class "Default")
      (node (ref "U$4") (pin "5") (pinfunction "5_5") (pintype "passive"))
    )
    (net (code "74") (name "unconnected-(U$4-Pad7)") (class "Default")
      (node (ref "U$4") (pin "7") (pinfunction "7_7") (pintype "passive"))
    )
    (net (code "75") (name "unconnected-(U$4-Pad9)") (class "Default")
      (node (ref "U$4") (pin "9") (pinfunction "9_9") (pintype "passive"))
    )
    (net (code "76") (name "unconnected-(U$4-Pad10)") (class "Default")
      (node (ref "U$4") (pin "10") (pinfunction "10_10") (pintype "passive"))
    )
    (net (code "77") (name "unconnected-(U$4-Pad11)") (class "Default")
      (node (ref "U$4") (pin "11") (pinfunction "11_11") (pintype "passive"))
    )
    (net (code "78") (name "unconnected-(U$4-Pad12)") (class "Default")
      (node (ref "U$4") (pin "12") (pinfunction "12_12") (pintype "passive"))
    )
    (net (code "79") (name "unconnected-(U$4-Pad13)") (class "Default")
      (node (ref "U$4") (pin "13") (pinfunction "13_13") (pintype "passive"))
    )
    (net (code "80") (name "unconnected-(U$4-Pad14)") (class "Default")
      (node (ref "U$4") (pin "14") (pinfunction "14_14") (pintype "passive"))
    )
    (net (code "81") (name "unconnected-(U$4-Pad15)") (class "Default")
      (node (ref "U$4") (pin "15") (pinfunction "15_15") (pintype "passive"))
    )
    (net (code "82") (name "unconnected-(U$4-Pad17)") (class "Default")
      (node (ref "U$4") (pin "17") (pinfunction "17_17") (pintype "passive"))
    )
    (net (code "83") (name "unconnected-(U$4-Pad19)") (class "Default")
      (node (ref "U$4") (pin "19") (pinfunction "19_19") (pintype "passive"))
    )
    (net (code "84") (name "unconnected-(U$4-Pad21)") (class "Default")
      (node (ref "U$4") (pin "21") (pinfunction "21_21") (pintype "passive"))
    )
    (net (code "85") (name "unconnected-(U$4-Pad23)") (class "Default")
      (node (ref "U$4") (pin "23") (pinfunction "23_23") (pintype "passive"))
    )
    (net (code "86") (name "unconnected-(U$4-Pad27)") (class "Default")
      (node (ref "U$4") (pin "27") (pinfunction "27_27") (pintype "passive"))
    )
    (net (code "87") (name "unconnected-(U$4-Pad29)") (class "Default")
      (node (ref "U$4") (pin "29") (pinfunction "29_29") (pintype "passive"))
    )
    (net (code "88") (name "unconnected-(U$4-Pad31)") (class "Default")
      (node (ref "U$4") (pin "31") (pinfunction "31_31") (pintype "passive"))
    )
    (net (code "89") (name "unconnected-(U$4-PadGND_PIEZO)") (class "Default")
      (node (ref "U$4") (pin "GND_PIEZO") (pinfunction "GND_PIEZO_GND_PIEZO") (pintype "passive"))
    )
    (net (code "90") (name "unconnected-(U$4-PadLED_PWM)") (class "Default")
      (node (ref "U$4") (pin "LED_PWM") (pinfunction "LED_PWM_LED_PWM") (pintype "passive"))
    )
    (net (code "91") (name "unconnected-(U$4-PadSERVO_PWM)") (class "Default")
      (node (ref "U$4") (pin "SERVO_PWM") (pinfunction "SERVO_PWM_SERVO_PWM") (pintype "passive"))
    )
    (net (code "92") (name "unconnected-(U$7-EN-Pad3)") (class "Default")
      (node (ref "U$7") (pin "3") (pinfunction "EN_3") (pintype "bidirectional"))
    )
    (net (code "93") (name "unconnected-(U2-GPI02-Pad17)") (class "Default")
      (node (ref "U2") (pin "17") (pinfunction "GPI02_17") (pintype "bidirectional"))
    )
    (net (code "94") (name "unconnected-(U2-GPIO0-Pad15)") (class "Default")
      (node (ref "U2") (pin "15") (pinfunction "GPIO0_15") (pintype "bidirectional"))
    )
    (net (code "95") (name "unconnected-(U2-GPIO1-Pad16)") (class "Default")
      (node (ref "U2") (pin "16") (pinfunction "GPIO1_16") (pintype "bidirectional"))
    )
    (net (code "96") (name "unconnected-(U2-GPIO3-Pad18)") (class "Default")
      (node (ref "U2") (pin "18") (pinfunction "GPIO3_18") (pintype "bidirectional"))
    )
    (net (code "97") (name "unconnected-(U2-XIN-Pad1)") (class "Default")
      (node (ref "U2") (pin "1") (pinfunction "XIN_1") (pintype "bidirectional"))
    )
    (net (code "98") (name "unconnected-(U2-XOUT-Pad24)") (class "Default")
      (node (ref "U2") (pin "24") (pinfunction "XOUT_24") (pintype "bidirectional"))
    )
    (net (code "99") (name "unconnected-(U2-~{CS}{slash}A0-Pad9)") (class "Default")
      (node (ref "U2") (pin "9") (pinfunction "~{CS}/A0_9") (pintype "bidirectional"))
    )
    (net (code "100") (name "unconnected-(U2-~{IRQ}-Pad11)") (class "Default")
      (node (ref "U2") (pin "11") (pinfunction "~{IRQ}_11") (pintype "bidirectional"))
    )
    (net (code "101") (name "unconnected-(U2-~{RTS}{slash}CLKOUT-Pad20)") (class "Default")
      (node (ref "U2") (pin "20") (pinfunction "~{RTS}/CLKOUT_20") (pintype "bidirectional"))
    )
    (net (code "102") (name "unconnected-(U7-NC1-Pad5)") (class "Default")
      (node (ref "U7") (pin "5") (pinfunction "NC1_5") (pintype "no_connect"))
    )
    (net (code "103") (name "unconnected-(U7-ON{slash}OFF-Pad7)") (class "Default")
      (node (ref "U7") (pin "7") (pinfunction "ON/OFF_7") (pintype "bidirectional"))
    )
  )
)
